# SYSTEM.net
KiCad netlist of a schematic drawn in Altium Designer
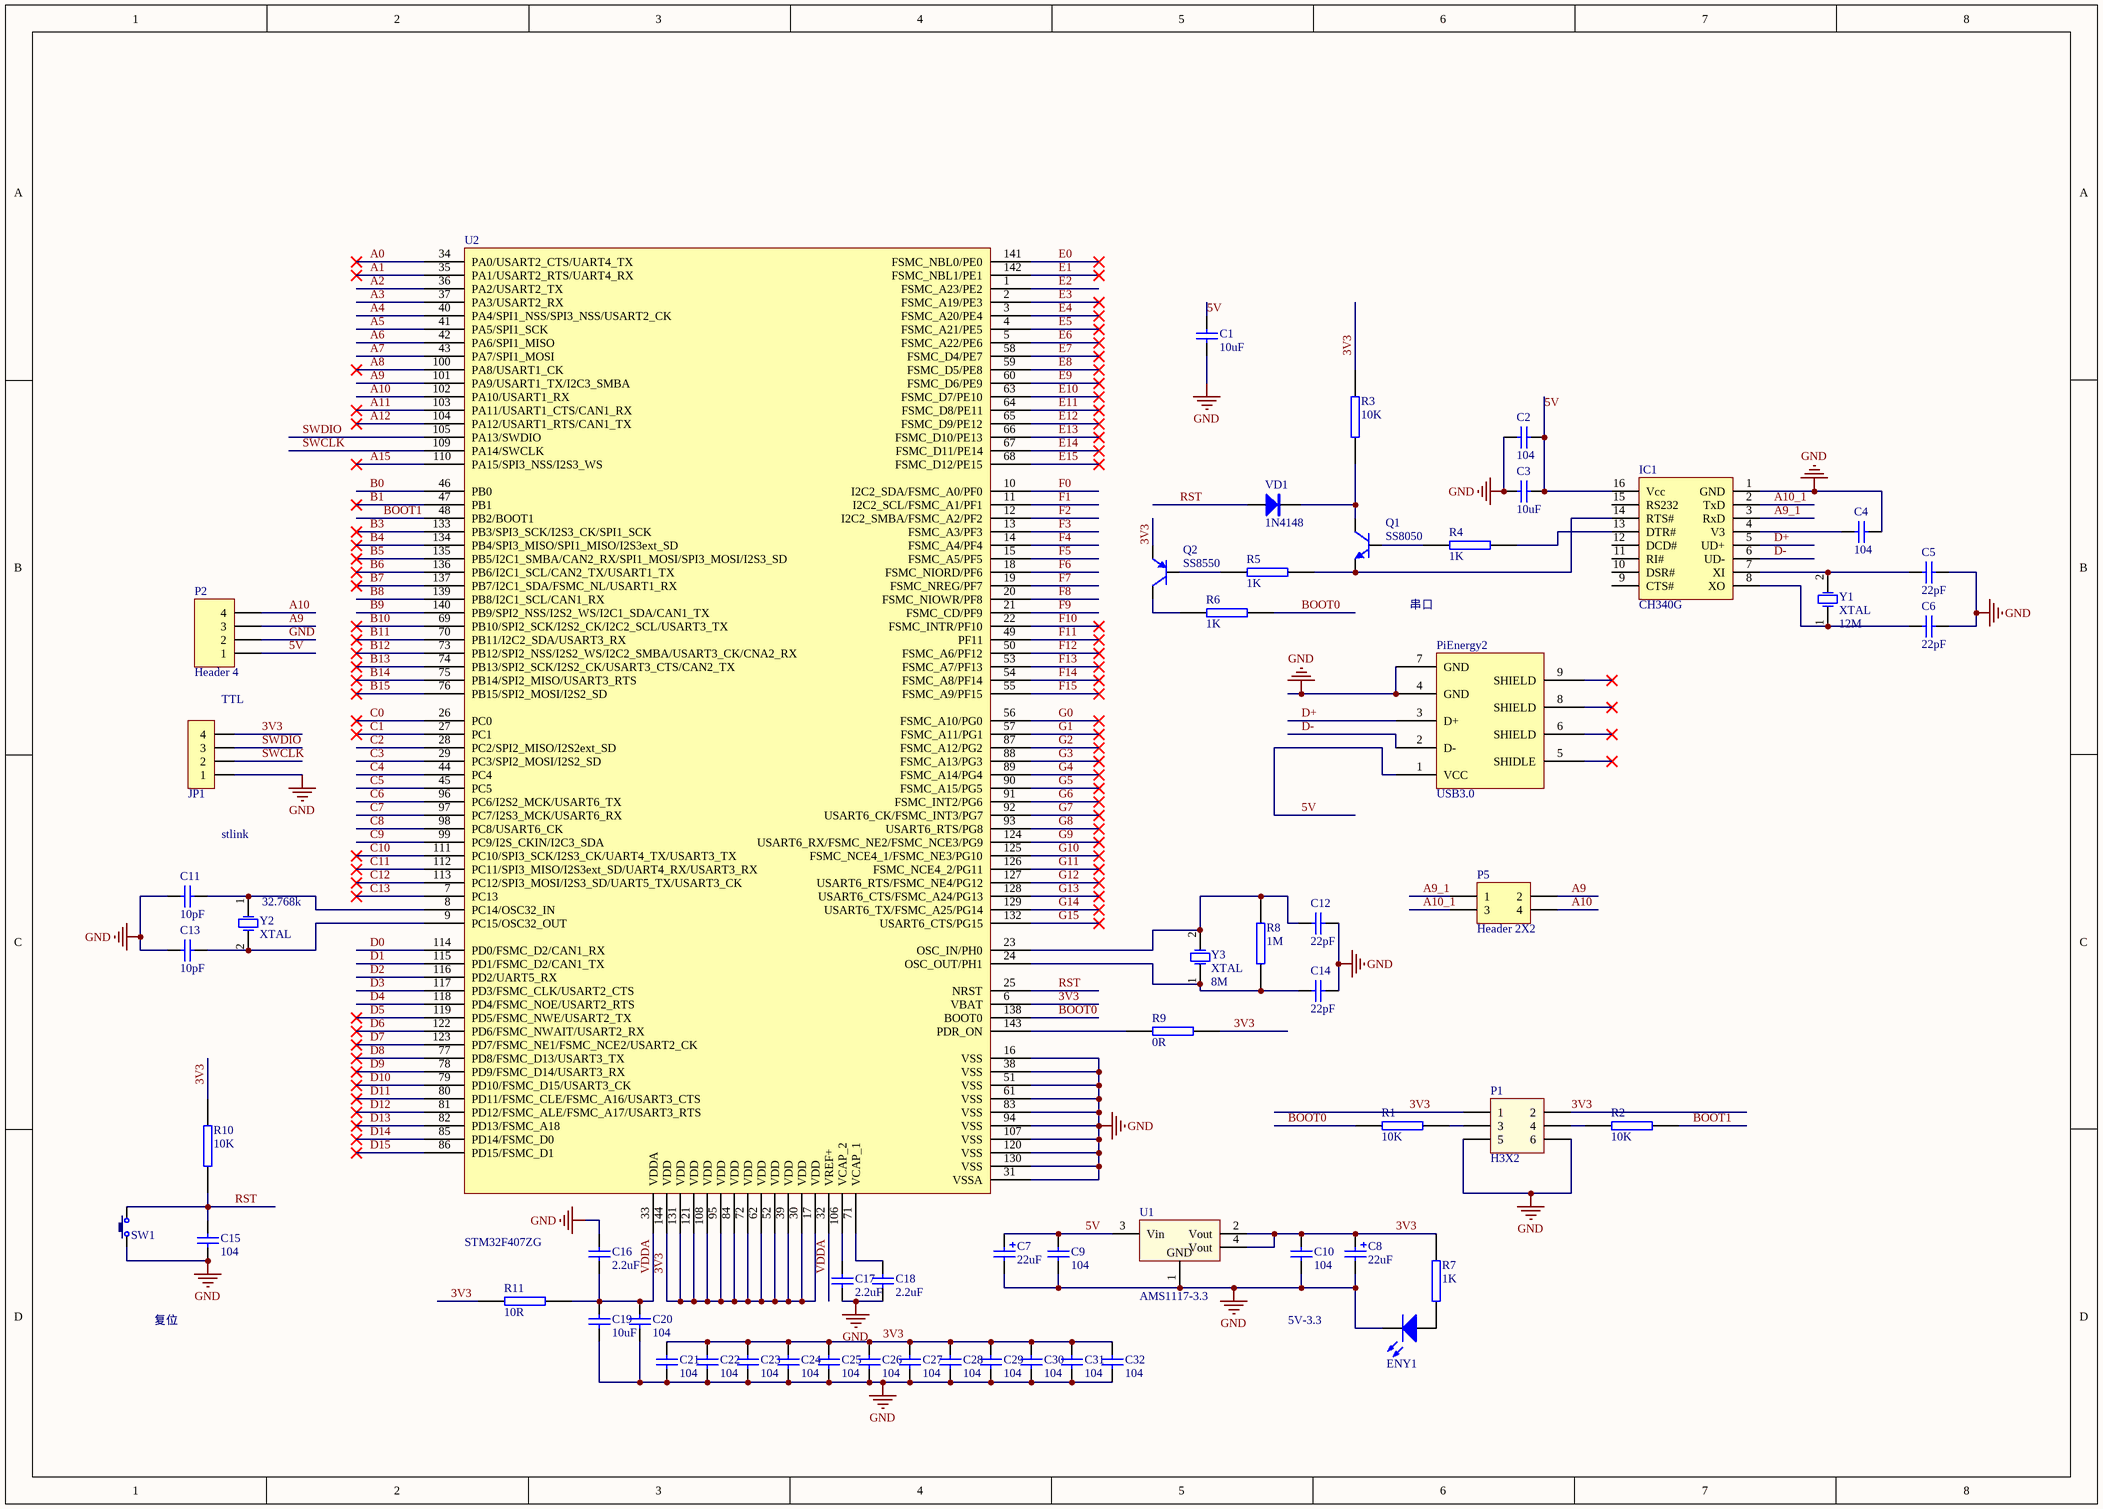
[diagram p0: SYSTEM.SchDoc]

(export (version "E")
  (design (tool "Eeschema 10.0.6"))
  (components
    (comp (ref "C1")
      (value "Cap")
      (footprint "CAP[0805]")
      (fields (field (name "ALTIUM_UNNAMED_1") "10uF"))
      (libsource (lib "STM32F103C8T6") (part "Cap"))
    )
    (comp (ref "C2")
      (value "Cap")
      (footprint "CAP[0805]")
      (fields (field (name "ALTIUM_UNNAMED_1") "104"))
      (libsource (lib "STM32F103C8T6") (part "Cap"))
    )
    (comp (ref "C3")
      (value "Cap")
      (footprint "CAP[0805]")
      (fields (field (name "ALTIUM_UNNAMED_1") "10uF"))
      (libsource (lib "STM32F103C8T6") (part "Cap"))
    )
    (comp (ref "C4")
      (value "Cap")
      (footprint "CAP[0805]")
      (fields (field (name "ALTIUM_UNNAMED_1") "104"))
      (libsource (lib "STM32F103C8T6") (part "Cap"))
    )
    (comp (ref "C5")
      (value "Cap")
      (footprint "CAP[0805]")
      (fields (field (name "ALTIUM_UNNAMED_1") "22pF"))
      (libsource (lib "STM32F103C8T6") (part "Cap"))
    )
    (comp (ref "C6")
      (value "Cap")
      (footprint "CAP[0805]")
      (fields (field (name "ALTIUM_UNNAMED_1") "22pF"))
      (libsource (lib "STM32F103C8T6") (part "Cap"))
    )
    (comp (ref "C7")
      (value "Cap Pol(22uF)")
      (footprint "CAP[1210]")
      (fields (field (name "ALTIUM_UNNAMED_1") "22uF"))
      (libsource (lib "STM32F103C8T6") (part "Cap Pol(22uF)"))
    )
    (comp (ref "C8")
      (value "Cap Pol(22uF)")
      (footprint "CAP[1210]")
      (fields (field (name "ALTIUM_UNNAMED_1") "22uF"))
      (libsource (lib "STM32F103C8T6") (part "Cap Pol(22uF)"))
    )
    (comp (ref "C9")
      (value "Cap")
      (footprint "CAP[0805]")
      (fields (field (name "ALTIUM_UNNAMED_1") "104"))
      (libsource (lib "STM32F103C8T6") (part "Cap"))
    )
    (comp (ref "C10")
      (value "Cap")
      (footprint "CAP[0805]")
      (fields (field (name "ALTIUM_UNNAMED_1") "104"))
      (libsource (lib "STM32F103C8T6") (part "Cap"))
    )
    (comp (ref "C11")
      (value "Cap")
      (footprint "CAP[0805]")
      (fields (field (name "ALTIUM_UNNAMED_1") "10pF"))
      (libsource (lib "STM32F103C8T6") (part "Cap"))
    )
    (comp (ref "C12")
      (value "Cap")
      (footprint "CAP[0805]")
      (fields (field (name "ALTIUM_UNNAMED_1") "22pF"))
      (libsource (lib "STM32F103C8T6") (part "Cap"))
    )
    (comp (ref "C13")
      (value "Cap")
      (footprint "CAP[0805]")
      (fields (field (name "ALTIUM_UNNAMED_1") "10pF"))
      (libsource (lib "STM32F103C8T6") (part "Cap"))
    )
    (comp (ref "C14")
      (value "Cap")
      (footprint "CAP[0805]")
      (fields (field (name "ALTIUM_UNNAMED_1") "22pF"))
      (libsource (lib "STM32F103C8T6") (part "Cap"))
    )
    (comp (ref "C15")
      (value "Cap")
      (footprint "CAP[0805]")
      (fields (field (name "ALTIUM_UNNAMED_1") "104"))
      (libsource (lib "STM32F103C8T6") (part "Cap"))
    )
    (comp (ref "C16")
      (value "Cap")
      (footprint "CAP[0805]")
      (fields (field (name "ALTIUM_UNNAMED_1") "2.2uF"))
      (libsource (lib "STM32F103C8T6") (part "Cap"))
    )
    (comp (ref "C17")
      (value "Cap")
      (footprint "CAP[0805]")
      (fields (field (name "ALTIUM_UNNAMED_1") "2.2uF"))
      (libsource (lib "STM32F103C8T6") (part "Cap"))
    )
    (comp (ref "C18")
      (value "Cap")
      (footprint "CAP[0805]")
      (fields (field (name "ALTIUM_UNNAMED_1") "2.2uF"))
      (libsource (lib "STM32F103C8T6") (part "Cap"))
    )
    (comp (ref "C19")
      (value "Cap")
      (footprint "CAP[0805]")
      (fields (field (name "ALTIUM_UNNAMED_1") "10uF"))
      (libsource (lib "STM32F103C8T6") (part "Cap"))
    )
    (comp (ref "C20")
      (value "Cap")
      (footprint "CAP[0805]")
      (fields (field (name "ALTIUM_UNNAMED_1") "104"))
      (libsource (lib "STM32F103C8T6") (part "Cap"))
    )
    (comp (ref "C21")
      (value "Cap")
      (footprint "CAP[0805]")
      (fields (field (name "ALTIUM_UNNAMED_1") "104"))
      (libsource (lib "STM32F103C8T6") (part "Cap"))
    )
    (comp (ref "C22")
      (value "Cap")
      (footprint "CAP[0805]")
      (fields (field (name "ALTIUM_UNNAMED_1") "104"))
      (libsource (lib "STM32F103C8T6") (part "Cap"))
    )
    (comp (ref "C23")
      (value "Cap")
      (footprint "CAP[0805]")
      (fields (field (name "ALTIUM_UNNAMED_1") "104"))
      (libsource (lib "STM32F103C8T6") (part "Cap"))
    )
    (comp (ref "C24")
      (value "Cap")
      (footprint "CAP[0805]")
      (fields (field (name "ALTIUM_UNNAMED_1") "104"))
      (libsource (lib "STM32F103C8T6") (part "Cap"))
    )
    (comp (ref "C25")
      (value "Cap")
      (footprint "CAP[0805]")
      (fields (field (name "ALTIUM_UNNAMED_1") "104"))
      (libsource (lib "STM32F103C8T6") (part "Cap"))
    )
    (comp (ref "C26")
      (value "Cap")
      (footprint "CAP[0805]")
      (fields (field (name "ALTIUM_UNNAMED_1") "104"))
      (libsource (lib "STM32F103C8T6") (part "Cap"))
    )
    (comp (ref "C27")
      (value "Cap")
      (footprint "CAP[0805]")
      (fields (field (name "ALTIUM_UNNAMED_1") "104"))
      (libsource (lib "STM32F103C8T6") (part "Cap"))
    )
    (comp (ref "C28")
      (value "Cap")
      (footprint "CAP[0805]")
      (fields (field (name "ALTIUM_UNNAMED_1") "104"))
      (libsource (lib "STM32F103C8T6") (part "Cap"))
    )
    (comp (ref "C29")
      (value "Cap")
      (footprint "CAP[0805]")
      (fields (field (name "ALTIUM_UNNAMED_1") "104"))
      (libsource (lib "STM32F103C8T6") (part "Cap"))
    )
    (comp (ref "C30")
      (value "Cap")
      (footprint "CAP[0805]")
      (fields (field (name "ALTIUM_UNNAMED_1") "104"))
      (libsource (lib "STM32F103C8T6") (part "Cap"))
    )
    (comp (ref "C31")
      (value "Cap")
      (footprint "CAP[0805]")
      (fields (field (name "ALTIUM_UNNAMED_1") "104"))
      (libsource (lib "STM32F103C8T6") (part "Cap"))
    )
    (comp (ref "C32")
      (value "Cap")
      (footprint "CAP[0805]")
      (fields (field (name "ALTIUM_UNNAMED_1") "104"))
      (libsource (lib "STM32F103C8T6") (part "Cap"))
    )
    (comp (ref "ENY1") (value "LED0") (footprint "LED[0805]") (libsource (lib "bob") (part "LED0")))
    (comp (ref "IC1")
      (value "CH340G")
      (footprint "SOP16_M")
      (description "串口转USB")
      (fields (field (name "版权归属") "源创客"))
      (libsource (lib "PCB_Project2") (part "CH340G"))
    )
    (comp (ref "JP1")
      (value "HDR-1X4")
      (footprint "HDR-1X4_M")
      (description "4P接插件")
      (fields (field (name "版权归属") "源创客"))
      (libsource (lib "PCB_Project2") (part "Header 4"))
    )
    (comp (ref "P1") (value "H3X2") (footprint "H2.54-2X3") (libsource (lib "STM32F103C8T6") (part "H3X2")))
    (comp (ref "P2")
      (value "Header 4")
      (footprint "HDR1X4")
      (description "Header, 4-Pin")
      (fields (field (name "PUBLISHER") "Altium Limited"))
      (libsource (lib "Miscellaneous Connectors") (part "Header 4"))
    )
    (comp (ref "P5")
      (value "Header 2X2")
      (footprint "HDR2X2")
      (description "Header, 2-Pin, Dual row")
      (fields (field (name "PUBLISHER") "Altium Limited"))
      (libsource (lib "Miscellaneous Connectors") (part "Header 2X2"))
    )
    (comp (ref "PiEnergy2") (value "USB3.0") (footprint "USB3.0") (libsource (lib "Robot") (part "USB3.0")))
    (comp (ref "Q1")
      (value "SS8050")
      (footprint "SOT23-3M")
      (description "高频放大-NPN型")
      (fields (field (name "版权归属") "源创客"))
      (libsource (lib "PCB_Project2") (part "8050-SMD"))
    )
    (comp (ref "Q2")
      (value "SS8550")
      (footprint "SOT23-3M")
      (description "高频放大-PNP型")
      (fields (field (name "版权归属") "源创客"))
      (libsource (lib "PCB_Project2") (part "8550-SMD"))
    )
    (comp (ref "R1") (value "10K") (footprint "R0805") (libsource (lib "STM32F103C8T6") (part "RES")))
    (comp (ref "R2") (value "10K") (footprint "R0805") (libsource (lib "STM32F103C8T6") (part "RES")))
    (comp (ref "R3") (value "10K") (footprint "R0805") (libsource (lib "STM32F103C8T6") (part "RES")))
    (comp (ref "R4") (value "1K") (footprint "R0805") (libsource (lib "STM32F103C8T6") (part "RES")))
    (comp (ref "R5") (value "1K") (footprint "R0805") (libsource (lib "STM32F103C8T6") (part "RES")))
    (comp (ref "R6") (value "1K") (footprint "R0805") (libsource (lib "STM32F103C8T6") (part "RES")))
    (comp (ref "R7") (value "1K") (footprint "R0805") (libsource (lib "bob") (part "RES")))
    (comp (ref "R8") (value "1M") (footprint "R0805") (libsource (lib "STM32F103C8T6") (part "RES")))
    (comp (ref "R9") (value "0R") (footprint "R0805") (libsource (lib "STM32F103C8T6") (part "RES")))
    (comp (ref "R10") (value "10K") (footprint "R0805") (libsource (lib "STM32F103C8T6") (part "RES")))
    (comp (ref "R11") (value "10R") (footprint "R0805") (libsource (lib "STM32F103C8T6") (part "RES")))
    (comp (ref "SW1")
      (value "3x6x5")
      (footprint "TSW SMD-3*6*2.5")
      (description "3x6轻触开关")
      (fields (field (name "版权归属") "源创客"))
      (libsource (lib "bob") (part "TSW 3x6"))
    )
    (comp (ref "U1")
      (value "AMS1117-3.3")
      (footprint "SOT-223(AMS1117-3.3)")
      (libsource (lib "STM32F103C8T6") (part "AMS1117-3.3"))
    )
    (comp (ref "U2")
      (value "STM32F407ZG")
      (footprint "LQFP144 20X20_M")
      (description "Flaah:1024/RAM:192/IO:114")
      (fields (field (name "版权归属") "源创客"))
      (libsource (lib "PCB_Project2") (part "STM32F407ZG"))
    )
    (comp (ref "VD1")
      (value "1N4148")
      (footprint "MINI_MELF (LL34)")
      (description "高速开关二极管")
      (fields (field (name "版权归属") "源创客"))
      (libsource (lib "PCB_Project2") (part "1N4148"))
    )
    (comp (ref "Y1")
      (value "XTAL")
      (footprint "XTAL")
      (fields (field (name "ALTIUM_UNNAMED_1") "12M"))
      (libsource (lib "STM32F103C8T6") (part "XTAL_1"))
    )
    (comp (ref "Y2")
      (value "XTAL")
      (footprint "XTAL-DT38-SMD")
      (fields (field (name "ALTIUM_UNNAMED_1") "32.768k"))
      (libsource (lib "STM32F103C8T6") (part "XTAL"))
    )
    (comp (ref "Y3")
      (value "XTAL")
      (footprint "XTAL")
      (fields (field (name "ALTIUM_UNNAMED_1") "8M"))
      (libsource (lib "STM32F103C8T6") (part "XTAL_1"))
    )
  )
  (nets
    (net (code "1") (name "/3V3") (class "Default")
      (node (ref "C10") (pin "2") (pinfunction "2_2") (pintype "passive"))
      (node (ref "C21") (pin "2") (pinfunction "2_2") (pintype "passive"))
      (node (ref "C22") (pin "2") (pinfunction "2_2") (pintype "passive"))
      (node (ref "C23") (pin "2") (pinfunction "2_2") (pintype "passive"))
      (node (ref "C24") (pin "2") (pinfunction "2_2") (pintype "passive"))
      (node (ref "C25") (pin "2") (pinfunction "2_2") (pintype "passive"))
      (node (ref "C26") (pin "2") (pinfunction "2_2") (pintype "passive"))
      (node (ref "C27") (pin "2") (pinfunction "2_2") (pintype "passive"))
      (node (ref "C28") (pin "2") (pinfunction "2_2") (pintype "passive"))
      (node (ref "C29") (pin "2") (pinfunction "2_2") (pintype "passive"))
      (node (ref "C30") (pin "2") (pinfunction "2_2") (pintype "passive"))
      (node (ref "C31") (pin "2") (pinfunction "2_2") (pintype "passive"))
      (node (ref "C32") (pin "2") (pinfunction "2_2") (pintype "passive"))
      (node (ref "C8") (pin "1") (pinfunction "1_1") (pintype "passive"))
      (node (ref "JP1") (pin "4") (pinfunction "4_4") (pintype "passive"))
      (node (ref "P1") (pin "1") (pinfunction "1_1") (pintype "passive"))
      (node (ref "P1") (pin "2") (pinfunction "2_2") (pintype "passive"))
      (node (ref "Q2") (pin "2") (pinfunction "E_2") (pintype "passive"))
      (node (ref "R10") (pin "2") (pinfunction "2_2") (pintype "passive"))
      (node (ref "R11") (pin "1") (pinfunction "1_1") (pintype "passive"))
      (node (ref "R3") (pin "2") (pinfunction "2_2") (pintype "passive"))
      (node (ref "R7") (pin "2") (pinfunction "2_2") (pintype "passive"))
      (node (ref "R9") (pin "2") (pinfunction "2_2") (pintype "passive"))
      (node (ref "U1") (pin "2") (pinfunction "Vout_2") (pintype "passive"))
      (node (ref "U1") (pin "4") (pinfunction "Vout_4") (pintype "passive"))
      (node (ref "U2") (pin "108") (pinfunction "VDD_108") (pintype "passive"))
      (node (ref "U2") (pin "121") (pinfunction "VDD_121") (pintype "passive"))
      (node (ref "U2") (pin "131") (pinfunction "VDD_131") (pintype "passive"))
      (node (ref "U2") (pin "144") (pinfunction "VDD_144") (pintype "passive"))
      (node (ref "U2") (pin "17") (pinfunction "VDD_17") (pintype "passive"))
      (node (ref "U2") (pin "30") (pinfunction "VDD_30") (pintype "passive"))
      (node (ref "U2") (pin "39") (pinfunction "VDD_39") (pintype "passive"))
      (node (ref "U2") (pin "52") (pinfunction "VDD_52") (pintype "passive"))
      (node (ref "U2") (pin "6") (pinfunction "VBAT_6") (pintype "passive"))
      (node (ref "U2") (pin "62") (pinfunction "VDD_62") (pintype "passive"))
      (node (ref "U2") (pin "72") (pinfunction "VDD_72") (pintype "passive"))
      (node (ref "U2") (pin "84") (pinfunction "VDD_84") (pintype "passive"))
      (node (ref "U2") (pin "95") (pinfunction "VDD_95") (pintype "passive"))
    )
    (net (code "2") (name "/5V") (class "Default")
      (node (ref "C1") (pin "2") (pinfunction "2_2") (pintype "passive"))
      (node (ref "C2") (pin "2") (pinfunction "2_2") (pintype "passive"))
      (node (ref "C3") (pin "2") (pinfunction "2_2") (pintype "passive"))
      (node (ref "C7") (pin "1") (pinfunction "1_1") (pintype "passive"))
      (node (ref "C9") (pin "2") (pinfunction "2_2") (pintype "passive"))
      (node (ref "IC1") (pin "16") (pinfunction "Vcc_16") (pintype "passive"))
      (node (ref "P2") (pin "1") (pinfunction "1_1") (pintype "passive"))
      (node (ref "PiEnergy2") (pin "1") (pinfunction "VCC_1") (pintype "passive"))
      (node (ref "U1") (pin "3") (pinfunction "Vin_3") (pintype "passive"))
    )
    (net (code "3") (name "/A0") (class "Default")
      (node (ref "U2") (pin "34") (pinfunction "PA0/USART2_CTS/UART4_TX_34") (pintype "passive+no_connect"))
    )
    (net (code "4") (name "/A1") (class "Default")
      (node (ref "U2") (pin "35") (pinfunction "PA1/USART2_RTS/UART4_RX_35") (pintype "passive+no_connect"))
    )
    (net (code "5") (name "/A2") (class "Default")
      (node (ref "U2") (pin "36") (pinfunction "PA2/USART2_TX_36") (pintype "passive"))
    )
    (net (code "6") (name "/A3") (class "Default")
      (node (ref "U2") (pin "37") (pinfunction "PA3/USART2_RX_37") (pintype "passive"))
    )
    (net (code "7") (name "/A4") (class "Default")
      (node (ref "U2") (pin "40") (pinfunction "PA4/SPI1_NSS/SPI3_NSS/USART2_CK_40") (pintype "passive"))
    )
    (net (code "8") (name "/A5") (class "Default")
      (node (ref "U2") (pin "41") (pinfunction "PA5/SPI1_SCK_41") (pintype "passive"))
    )
    (net (code "9") (name "/A6") (class "Default")
      (node (ref "U2") (pin "42") (pinfunction "PA6/SPI1_MISO_42") (pintype "passive"))
    )
    (net (code "10") (name "/A7") (class "Default")
      (node (ref "U2") (pin "43") (pinfunction "PA7/SPI1_MOSI_43") (pintype "passive"))
    )
    (net (code "11") (name "/A8") (class "Default")
      (node (ref "U2") (pin "100") (pinfunction "PA8/USART1_CK_100") (pintype "passive+no_connect"))
    )
    (net (code "12") (name "/A9") (class "Default")
      (node (ref "P2") (pin "3") (pinfunction "3_3") (pintype "passive"))
      (node (ref "P5") (pin "2") (pinfunction "2_2") (pintype "passive"))
      (node (ref "U2") (pin "101") (pinfunction "PA9/USART1_TX/I2C3_SMBA_101") (pintype "passive"))
    )
    (net (code "13") (name "/A9_1") (class "Default")
      (node (ref "IC1") (pin "3") (pinfunction "RxD_3") (pintype "passive"))
      (node (ref "P5") (pin "1") (pinfunction "1_1") (pintype "passive"))
    )
    (net (code "14") (name "/A10") (class "Default")
      (node (ref "P2") (pin "4") (pinfunction "4_4") (pintype "passive"))
      (node (ref "P5") (pin "4") (pinfunction "4_4") (pintype "passive"))
      (node (ref "U2") (pin "102") (pinfunction "PA10/USART1_RX_102") (pintype "passive"))
    )
    (net (code "15") (name "/A10_1") (class "Default")
      (node (ref "IC1") (pin "2") (pinfunction "TxD_2") (pintype "passive"))
      (node (ref "P5") (pin "3") (pinfunction "3_3") (pintype "passive"))
    )
    (net (code "16") (name "/A11") (class "Default")
      (node (ref "U2") (pin "103") (pinfunction "PA11/USART1_CTS/CAN1_RX_103") (pintype "passive+no_connect"))
    )
    (net (code "17") (name "/A12") (class "Default")
      (node (ref "U2") (pin "104") (pinfunction "PA12/USART1_RTS/CAN1_TX_104") (pintype "passive+no_connect"))
    )
    (net (code "18") (name "/A15") (class "Default")
      (node (ref "U2") (pin "110") (pinfunction "PA15/SPI3_NSS/I2S3_WS_110") (pintype "passive+no_connect"))
    )
    (net (code "19") (name "/B0") (class "Default")
      (node (ref "U2") (pin "46") (pinfunction "PB0_46") (pintype "passive"))
    )
    (net (code "20") (name "/B1") (class "Default")
      (node (ref "U2") (pin "47") (pinfunction "PB1_47") (pintype "passive+no_connect"))
    )
    (net (code "21") (name "/B3") (class "Default")
      (node (ref "U2") (pin "133") (pinfunction "PB3/SPI3_SCK/I2S3_CK/SPI1_SCK_133") (pintype "passive+no_connect"))
    )
    (net (code "22") (name "/B4") (class "Default")
      (node (ref "U2") (pin "134") (pinfunction "PB4/SPI3_MISO/SPI1_MISO/I2S3ext_SD_134") (pintype "passive+no_connect"))
    )
    (net (code "23") (name "/B5") (class "Default")
      (node (ref "U2") (pin "135") (pinfunction "PB5/I2C1_SMBA/CAN2_RX/SPI1_MOSI/SPI3_MOSI/I2S3_SD_135") (pintype "passive+no_connect"))
    )
    (net (code "24") (name "/B6") (class "Default")
      (node (ref "U2") (pin "136") (pinfunction "PB6/I2C1_SCL/CAN2_TX/USART1_TX_136") (pintype "passive+no_connect"))
    )
    (net (code "25") (name "/B7") (class "Default")
      (node (ref "U2") (pin "137") (pinfunction "PB7/I2C1_SDA/FSMC_NL/USART1_RX_137") (pintype "passive+no_connect"))
    )
    (net (code "26") (name "/B8") (class "Default")
      (node (ref "U2") (pin "139") (pinfunction "PB8/I2C1_SCL/CAN1_RX_139") (pintype "passive"))
    )
    (net (code "27") (name "/B9") (class "Default")
      (node (ref "U2") (pin "140") (pinfunction "PB9/SPI2_NSS/I2S2_WS/I2C1_SDA/CAN1_TX_140") (pintype "passive"))
    )
    (net (code "28") (name "/B10") (class "Default")
      (node (ref "U2") (pin "69") (pinfunction "PB10/SPI2_SCK/I2S2_CK/I2C2_SCL/USART3_TX_69") (pintype "passive+no_connect"))
    )
    (net (code "29") (name "/B11") (class "Default")
      (node (ref "U2") (pin "70") (pinfunction "PB11/I2C2_SDA/USART3_RX_70") (pintype "passive+no_connect"))
    )
    (net (code "30") (name "/B12") (class "Default")
      (node (ref "U2") (pin "73") (pinfunction "PB12/SPI2_NSS/I2S2_WS/I2C2_SMBA/USART3_CK/CNA2_RX_73") (pintype "passive+no_connect"))
    )
    (net (code "31") (name "/B13") (class "Default")
      (node (ref "U2") (pin "74") (pinfunction "PB13/SPI2_SCK/I2S2_CK/USART3_CTS/CAN2_TX_74") (pintype "passive+no_connect"))
    )
    (net (code "32") (name "/B14") (class "Default")
      (node (ref "U2") (pin "75") (pinfunction "PB14/SPI2_MISO/USART3_RTS_75") (pintype "passive+no_connect"))
    )
    (net (code "33") (name "/B15") (class "Default")
      (node (ref "U2") (pin "76") (pinfunction "PB15/SPI2_MOSI/I2S2_SD_76") (pintype "passive+no_connect"))
    )
    (net (code "34") (name "/BOOT0") (class "Default")
      (node (ref "R1") (pin "1") (pinfunction "1_1") (pintype "passive"))
      (node (ref "R6") (pin "1") (pinfunction "1_1") (pintype "passive"))
      (node (ref "U2") (pin "138") (pinfunction "BOOT0_138") (pintype "passive"))
    )
    (net (code "35") (name "/BOOT1") (class "Default")
      (node (ref "R2") (pin "2") (pinfunction "2_2") (pintype "passive"))
      (node (ref "U2") (pin "48") (pinfunction "PB2/BOOT1_48") (pintype "passive"))
    )
    (net (code "36") (name "/C0") (class "Default")
      (node (ref "U2") (pin "26") (pinfunction "PC0_26") (pintype "passive+no_connect"))
    )
    (net (code "37") (name "/C1") (class "Default")
      (node (ref "U2") (pin "27") (pinfunction "PC1_27") (pintype "passive+no_connect"))
    )
    (net (code "38") (name "/C2") (class "Default")
      (node (ref "U2") (pin "28") (pinfunction "PC2/SPI2_MISO/I2S2ext_SD_28") (pintype "passive"))
    )
    (net (code "39") (name "/C3") (class "Default")
      (node (ref "U2") (pin "29") (pinfunction "PC3/SPI2_MOSI/I2S2_SD_29") (pintype "passive"))
    )
    (net (code "40") (name "/C4") (class "Default")
      (node (ref "U2") (pin "44") (pinfunction "PC4_44") (pintype "passive"))
    )
    (net (code "41") (name "/C5") (class "Default")
      (node (ref "U2") (pin "45") (pinfunction "PC5_45") (pintype "passive"))
    )
    (net (code "42") (name "/C6") (class "Default")
      (node (ref "U2") (pin "96") (pinfunction "PC6/I2S2_MCK/USART6_TX_96") (pintype "passive"))
    )
    (net (code "43") (name "/C7") (class "Default")
      (node (ref "U2") (pin "97") (pinfunction "PC7/I2S3_MCK/USART6_RX_97") (pintype "passive"))
    )
    (net (code "44") (name "/C8") (class "Default")
      (node (ref "U2") (pin "98") (pinfunction "PC8/USART6_CK_98") (pintype "passive"))
    )
    (net (code "45") (name "/C9") (class "Default")
      (node (ref "U2") (pin "99") (pinfunction "PC9/I2S_CKIN/I2C3_SDA_99") (pintype "passive"))
    )
    (net (code "46") (name "/C10") (class "Default")
      (node (ref "U2") (pin "111") (pinfunction "PC10/SPI3_SCK/I2S3_CK/UART4_TX/USART3_TX_111") (pintype "passive+no_connect"))
    )
    (net (code "47") (name "/C11") (class "Default")
      (node (ref "U2") (pin "112") (pinfunction "PC11/SPI3_MISO/I2S3ext_SD/UART4_RX/USART3_RX_112") (pintype "passive+no_connect"))
    )
    (net (code "48") (name "/C12") (class "Default")
      (node (ref "U2") (pin "113") (pinfunction "PC12/SPI3_MOSI/I2S3_SD/UART5_TX/USART3_CK_113") (pintype "passive+no_connect"))
    )
    (net (code "49") (name "/C13") (class "Default")
      (node (ref "U2") (pin "7") (pinfunction "PC13_7") (pintype "passive+no_connect"))
    )
    (net (code "50") (name "/D+") (class "Default")
      (node (ref "IC1") (pin "5") (pinfunction "UD+_5") (pintype "passive"))
      (node (ref "PiEnergy2") (pin "3") (pinfunction "D+_3") (pintype "passive"))
    )
    (net (code "51") (name "/D-") (class "Default")
      (node (ref "IC1") (pin "6") (pinfunction "UD-_6") (pintype "passive"))
      (node (ref "PiEnergy2") (pin "2") (pinfunction "D-_2") (pintype "passive"))
    )
    (net (code "52") (name "/D0") (class "Default")
      (node (ref "U2") (pin "114") (pinfunction "PD0/FSMC_D2/CAN1_RX_114") (pintype "passive"))
    )
    (net (code "53") (name "/D1") (class "Default")
      (node (ref "U2") (pin "115") (pinfunction "PD1/FSMC_D2/CAN1_TX_115") (pintype "passive"))
    )
    (net (code "54") (name "/D2") (class "Default")
      (node (ref "U2") (pin "116") (pinfunction "PD2/UART5_RX_116") (pintype "passive"))
    )
    (net (code "55") (name "/D3") (class "Default")
      (node (ref "U2") (pin "117") (pinfunction "PD3/FSMC_CLK/USART2_CTS_117") (pintype "passive"))
    )
    (net (code "56") (name "/D4") (class "Default")
      (node (ref "U2") (pin "118") (pinfunction "PD4/FSMC_NOE/USART2_RTS_118") (pintype "passive"))
    )
    (net (code "57") (name "/D5") (class "Default")
      (node (ref "U2") (pin "119") (pinfunction "PD5/FSMC_NWE/USART2_TX_119") (pintype "passive+no_connect"))
    )
    (net (code "58") (name "/D6") (class "Default")
      (node (ref "U2") (pin "122") (pinfunction "PD6/FSMC_NWAIT/USART2_RX_122") (pintype "passive+no_connect"))
    )
    (net (code "59") (name "/D7") (class "Default")
      (node (ref "U2") (pin "123") (pinfunction "PD7/FSMC_NE1/FSMC_NCE2/USART2_CK_123") (pintype "passive+no_connect"))
    )
    (net (code "60") (name "/D8") (class "Default")
      (node (ref "U2") (pin "77") (pinfunction "PD8/FSMC_D13/USART3_TX_77") (pintype "passive+no_connect"))
    )
    (net (code "61") (name "/D9") (class "Default")
      (node (ref "U2") (pin "78") (pinfunction "PD9/FSMC_D14/USART3_RX_78") (pintype "passive+no_connect"))
    )
    (net (code "62") (name "/D10") (class "Default")
      (node (ref "U2") (pin "79") (pinfunction "PD10/FSMC_D15/USART3_CK_79") (pintype "passive+no_connect"))
    )
    (net (code "63") (name "/D11") (class "Default")
      (node (ref "U2") (pin "80") (pinfunction "PD11/FSMC_CLE/FSMC_A16/USART3_CTS_80") (pintype "passive+no_connect"))
    )
    (net (code "64") (name "/D12") (class "Default")
      (node (ref "U2") (pin "81") (pinfunction "PD12/FSMC_ALE/FSMC_A17/USART3_RTS_81") (pintype "passive+no_connect"))
    )
    (net (code "65") (name "/D13") (class "Default")
      (node (ref "U2") (pin "82") (pinfunction "PD13/FSMC_A18_82") (pintype "passive+no_connect"))
    )
    (net (code "66") (name "/D14") (class "Default")
      (node (ref "U2") (pin "85") (pinfunction "PD14/FSMC_D0_85") (pintype "passive+no_connect"))
    )
    (net (code "67") (name "/D15") (class "Default")
      (node (ref "U2") (pin "86") (pinfunction "PD15/FSMC_D1_86") (pintype "passive+no_connect"))
    )
    (net (code "68") (name "/E0") (class "Default")
      (node (ref "U2") (pin "141") (pinfunction "FSMC_NBL0/PE0_141") (pintype "passive+no_connect"))
    )
    (net (code "69") (name "/E1") (class "Default")
      (node (ref "U2") (pin "142") (pinfunction "FSMC_NBL1/PE1_142") (pintype "passive+no_connect"))
    )
    (net (code "70") (name "/E2") (class "Default")
      (node (ref "U2") (pin "1") (pinfunction "FSMC_A23/PE2_1") (pintype "passive"))
    )
    (net (code "71") (name "/E3") (class "Default")
      (node (ref "U2") (pin "2") (pinfunction "FSMC_A19/PE3_2") (pintype "passive+no_connect"))
    )
    (net (code "72") (name "/E4") (class "Default")
      (node (ref "U2") (pin "3") (pinfunction "FSMC_A20/PE4_3") (pintype "passive+no_connect"))
    )
    (net (code "73") (name "/E5") (class "Default")
      (node (ref "U2") (pin "4") (pinfunction "FSMC_A21/PE5_4") (pintype "passive+no_connect"))
    )
    (net (code "74") (name "/E6") (class "Default")
      (node (ref "U2") (pin "5") (pinfunction "FSMC_A22/PE6_5") (pintype "passive+no_connect"))
    )
    (net (code "75") (name "/E7") (class "Default")
      (node (ref "U2") (pin "58") (pinfunction "FSMC_D4/PE7_58") (pintype "passive+no_connect"))
    )
    (net (code "76") (name "/E8") (class "Default")
      (node (ref "U2") (pin "59") (pinfunction "FSMC_D5/PE8_59") (pintype "passive+no_connect"))
    )
    (net (code "77") (name "/E9") (class "Default")
      (node (ref "U2") (pin "60") (pinfunction "FSMC_D6/PE9_60") (pintype "passive+no_connect"))
    )
    (net (code "78") (name "/E10") (class "Default")
      (node (ref "U2") (pin "63") (pinfunction "FSMC_D7/PE10_63") (pintype "passive+no_connect"))
    )
    (net (code "79") (name "/E11") (class "Default")
      (node (ref "U2") (pin "64") (pinfunction "FSMC_D8/PE11_64") (pintype "passive+no_connect"))
    )
    (net (code "80") (name "/E12") (class "Default")
      (node (ref "U2") (pin "65") (pinfunction "FSMC_D9/PE12_65") (pintype "passive+no_connect"))
    )
    (net (code "81") (name "/E13") (class "Default")
      (node (ref "U2") (pin "66") (pinfunction "FSMC_D10/PE13_66") (pintype "passive+no_connect"))
    )
    (net (code "82") (name "/E14") (class "Default")
      (node (ref "U2") (pin "67") (pinfunction "FSMC_D11/PE14_67") (pintype "passive+no_connect"))
    )
    (net (code "83") (name "/E15") (class "Default")
      (node (ref "U2") (pin "68") (pinfunction "FSMC_D12/PE15_68") (pintype "passive+no_connect"))
    )
    (net (code "84") (name "/F0") (class "Default")
      (node (ref "U2") (pin "10") (pinfunction "I2C2_SDA/FSMC_A0/PF0_10") (pintype "passive"))
    )
    (net (code "85") (name "/F1") (class "Default")
      (node (ref "U2") (pin "11") (pinfunction "I2C2_SCL/FSMC_A1/PF1_11") (pintype "passive"))
    )
    (net (code "86") (name "/F2") (class "Default")
      (node (ref "U2") (pin "12") (pinfunction "I2C2_SMBA/FSMC_A2/PF2_12") (pintype "passive"))
    )
    (net (code "87") (name "/F3") (class "Default")
      (node (ref "U2") (pin "13") (pinfunction "FSMC_A3/PF3_13") (pintype "passive"))
    )
    (net (code "88") (name "/F4") (class "Default")
      (node (ref "U2") (pin "14") (pinfunction "FSMC_A4/PF4_14") (pintype "passive"))
    )
    (net (code "89") (name "/F5") (class "Default")
      (node (ref "U2") (pin "15") (pinfunction "FSMC_A5/PF5_15") (pintype "passive"))
    )
    (net (code "90") (name "/F6") (class "Default")
      (node (ref "U2") (pin "18") (pinfunction "FSMC_NIORD/PF6_18") (pintype "passive"))
    )
    (net (code "91") (name "/F7") (class "Default")
      (node (ref "U2") (pin "19") (pinfunction "FSMC_NREG/PF7_19") (pintype "passive"))
    )
    (net (code "92") (name "/F8") (class "Default")
      (node (ref "U2") (pin "20") (pinfunction "FSMC_NIOWR/PF8_20") (pintype "passive"))
    )
    (net (code "93") (name "/F9") (class "Default")
      (node (ref "U2") (pin "21") (pinfunction "FSMC_CD/PF9_21") (pintype "passive"))
    )
    (net (code "94") (name "/F10") (class "Default")
      (node (ref "U2") (pin "22") (pinfunction "FSMC_INTR/PF10_22") (pintype "passive+no_connect"))
    )
    (net (code "95") (name "/F11") (class "Default")
      (node (ref "U2") (pin "49") (pinfunction "PF11_49") (pintype "passive+no_connect"))
    )
    (net (code "96") (name "/F12") (class "Default")
      (node (ref "U2") (pin "50") (pinfunction "FSMC_A6/PF12_50") (pintype "passive+no_connect"))
    )
    (net (code "97") (name "/F13") (class "Default")
      (node (ref "U2") (pin "53") (pinfunction "FSMC_A7/PF13_53") (pintype "passive+no_connect"))
    )
    (net (code "98") (name "/F14") (class "Default")
      (node (ref "U2") (pin "54") (pinfunction "FSMC_A8/PF14_54") (pintype "passive+no_connect"))
    )
    (net (code "99") (name "/F15") (class "Default")
      (node (ref "U2") (pin "55") (pinfunction "FSMC_A9/PF15_55") (pintype "passive+no_connect"))
    )
    (net (code "100") (name "/G0") (class "Default")
      (node (ref "U2") (pin "56") (pinfunction "FSMC_A10/PG0_56") (pintype "passive+no_connect"))
    )
    (net (code "101") (name "/G1") (class "Default")
      (node (ref "U2") (pin "57") (pinfunction "FSMC_A11/PG1_57") (pintype "passive+no_connect"))
    )
    (net (code "102") (name "/G2") (class "Default")
      (node (ref "U2") (pin "87") (pinfunction "FSMC_A12/PG2_87") (pintype "passive+no_connect"))
    )
    (net (code "103") (name "/G3") (class "Default")
      (node (ref "U2") (pin "88") (pinfunction "FSMC_A13/PG3_88") (pintype "passive+no_connect"))
    )
    (net (code "104") (name "/G4") (class "Default")
      (node (ref "U2") (pin "89") (pinfunction "FSMC_A14/PG4_89") (pintype "passive+no_connect"))
    )
    (net (code "105") (name "/G5") (class "Default")
      (node (ref "U2") (pin "90") (pinfunction "FSMC_A15/PG5_90") (pintype "passive+no_connect"))
    )
    (net (code "106") (name "/G6") (class "Default")
      (node (ref "U2") (pin "91") (pinfunction "FSMC_INT2/PG6_91") (pintype "passive+no_connect"))
    )
    (net (code "107") (name "/G7") (class "Default")
      (node (ref "U2") (pin "92") (pinfunction "USART6_CK/FSMC_INT3/PG7_92") (pintype "passive+no_connect"))
    )
    (net (code "108") (name "/G8") (class "Default")
      (node (ref "U2") (pin "93") (pinfunction "USART6_RTS/PG8_93") (pintype "passive+no_connect"))
    )
    (net (code "109") (name "/G9") (class "Default")
      (node (ref "U2") (pin "124") (pinfunction "USART6_RX/FSMC_NE2/FSMC_NCE3/PG9_124") (pintype "passive+no_connect"))
    )
    (net (code "110") (name "/G10") (class "Default")
      (node (ref "U2") (pin "125") (pinfunction "FSMC_NCE4_1/FSMC_NE3/PG10_125") (pintype "passive+no_connect"))
    )
    (net (code "111") (name "/G11") (class "Default")
      (node (ref "U2") (pin "126") (pinfunction "FSMC_NCE4_2/PG11_126") (pintype "passive+no_connect"))
    )
    (net (code "112") (name "/G12") (class "Default")
      (node (ref "U2") (pin "127") (pinfunction "USART6_RTS/FSMC_NE4/PG12_127") (pintype "passive+no_connect"))
    )
    (net (code "113") (name "/G13") (class "Default")
      (node (ref "U2") (pin "128") (pinfunction "USART6_CTS/FSMC_A24/PG13_128") (pintype "passive+no_connect"))
    )
    (net (code "114") (name "/G14") (class "Default")
      (node (ref "U2") (pin "129") (pinfunction "USART6_TX/FSMC_A25/PG14_129") (pintype "passive+no_connect"))
    )
    (net (code "115") (name "/G15") (class "Default")
      (node (ref "U2") (pin "132") (pinfunction "USART6_CTS/PG15_132") (pintype "passive+no_connect"))
    )
    (net (code "116") (name "/RST") (class "Default")
      (node (ref "C15") (pin "2") (pinfunction "2_2") (pintype "passive"))
      (node (ref "R10") (pin "1") (pinfunction "1_1") (pintype "passive"))
      (node (ref "SW1") (pin "2") (pinfunction "2_2") (pintype "passive"))
      (node (ref "U2") (pin "25") (pinfunction "NRST_25") (pintype "passive"))
      (node (ref "VD1") (pin "1") (pinfunction "A_1") (pintype "passive"))
    )
    (net (code "117") (name "/SWCLK") (class "Default")
      (node (ref "JP1") (pin "2") (pinfunction "2_2") (pintype "passive"))
      (node (ref "U2") (pin "109") (pinfunction "PA14/SWCLK_109") (pintype "passive"))
    )
    (net (code "118") (name "/SWDIO") (class "Default")
      (node (ref "JP1") (pin "3") (pinfunction "3_3") (pintype "passive"))
      (node (ref "U2") (pin "105") (pinfunction "PA13/SWDIO_105") (pintype "passive"))
    )
    (net (code "119") (name "/VDDA") (class "Default")
      (node (ref "C16") (pin "1") (pinfunction "1_1") (pintype "passive"))
      (node (ref "C19") (pin "2") (pinfunction "2_2") (pintype "passive"))
      (node (ref "C20") (pin "2") (pinfunction "2_2") (pintype "passive"))
      (node (ref "R11") (pin "2") (pinfunction "2_2") (pintype "passive"))
      (node (ref "U2") (pin "32") (pinfunction "VREF+_32") (pintype "passive"))
      (node (ref "U2") (pin "33") (pinfunction "VDDA_33") (pintype "passive"))
    )
    (net (code "120") (name "GND") (class "Default")
      (node (ref "C1") (pin "1") (pinfunction "1_1") (pintype "passive"))
      (node (ref "C10") (pin "1") (pinfunction "1_1") (pintype "passive"))
      (node (ref "C11") (pin "1") (pinfunction "1_1") (pintype "passive"))
      (node (ref "C12") (pin "2") (pinfunction "2_2") (pintype "passive"))
      (node (ref "C13") (pin "1") (pinfunction "1_1") (pintype "passive"))
      (node (ref "C14") (pin "2") (pinfunction "2_2") (pintype "passive"))
      (node (ref "C15") (pin "1") (pinfunction "1_1") (pintype "passive"))
      (node (ref "C16") (pin "2") (pinfunction "2_2") (pintype "passive"))
      (node (ref "C17") (pin "1") (pinfunction "1_1") (pintype "passive"))
      (node (ref "C18") (pin "1") (pinfunction "1_1") (pintype "passive"))
      (node (ref "C19") (pin "1") (pinfunction "1_1") (pintype "passive"))
      (node (ref "C2") (pin "1") (pinfunction "1_1") (pintype "passive"))
      (node (ref "C20") (pin "1") (pinfunction "1_1") (pintype "passive"))
      (node (ref "C21") (pin "1") (pinfunction "1_1") (pintype "passive"))
      (node (ref "C22") (pin "1") (pinfunction "1_1") (pintype "passive"))
      (node (ref "C23") (pin "1") (pinfunction "1_1") (pintype "passive"))
      (node (ref "C24") (pin "1") (pinfunction "1_1") (pintype "passive"))
      (node (ref "C25") (pin "1") (pinfunction "1_1") (pintype "passive"))
      (node (ref "C26") (pin "1") (pinfunction "1_1") (pintype "passive"))
      (node (ref "C27") (pin "1") (pinfunction "1_1") (pintype "passive"))
      (node (ref "C28") (pin "1") (pinfunction "1_1") (pintype "passive"))
      (node (ref "C29") (pin "1") (pinfunction "1_1") (pintype "passive"))
      (node (ref "C3") (pin "1") (pinfunction "1_1") (pintype "passive"))
      (node (ref "C30") (pin "1") (pinfunction "1_1") (pintype "passive"))
      (node (ref "C31") (pin "1") (pinfunction "1_1") (pintype "passive"))
      (node (ref "C32") (pin "1") (pinfunction "1_1") (pintype "passive"))
      (node (ref "C4") (pin "2") (pinfunction "2_2") (pintype "passive"))
      (node (ref "C5") (pin "2") (pinfunction "2_2") (pintype "passive"))
      (node (ref "C6") (pin "2") (pinfunction "2_2") (pintype "passive"))
      (node (ref "C7") (pin "2") (pinfunction "2_2") (pintype "passive"))
      (node (ref "C8") (pin "2") (pinfunction "2_2") (pintype "passive"))
      (node (ref "C9") (pin "1") (pinfunction "1_1") (pintype "passive"))
      (node (ref "ENY1") (pin "2") (pinfunction "K_2") (pintype "passive"))
      (node (ref "IC1") (pin "1") (pinfunction "GND_1") (pintype "passive"))
      (node (ref "JP1") (pin "1") (pinfunction "1_1") (pintype "passive"))
      (node (ref "P1") (pin "5") (pinfunction "5_5") (pintype "passive"))
      (node (ref "P1") (pin "6") (pinfunction "6_6") (pintype "passive"))
      (node (ref "P2") (pin "2") (pinfunction "2_2") (pintype "passive"))
      (node (ref "PiEnergy2") (pin "4") (pinfunction "GND_4") (pintype "passive"))
      (node (ref "PiEnergy2") (pin "7") (pinfunction "GND_7") (pintype "passive"))
      (node (ref "SW1") (pin "1") (pinfunction "1_1") (pintype "passive"))
      (node (ref "U1") (pin "1") (pinfunction "GND_1") (pintype "passive"))
      (node (ref "U2") (pin "107") (pinfunction "VSS_107") (pintype "passive"))
      (node (ref "U2") (pin "120") (pinfunction "VSS_120") (pintype "passive"))
      (node (ref "U2") (pin "130") (pinfunction "VSS_130") (pintype "passive"))
      (node (ref "U2") (pin "16") (pinfunction "VSS_16") (pintype "passive"))
      (node (ref "U2") (pin "31") (pinfunction "VSSA_31") (pintype "passive"))
      (node (ref "U2") (pin "38") (pinfunction "VSS_38") (pintype "passive"))
      (node (ref "U2") (pin "51") (pinfunction "VSS_51") (pintype "passive"))
      (node (ref "U2") (pin "61") (pinfunction "VSS_61") (pintype "passive"))
      (node (ref "U2") (pin "83") (pinfunction "VSS_83") (pintype "passive"))
      (node (ref "U2") (pin "94") (pinfunction "VSS_94") (pintype "passive"))
    )
    (net (code "121") (name "Net-(ENY1-A)") (class "Default")
      (node (ref "ENY1") (pin "1") (pinfunction "A_1") (pintype "passive"))
      (node (ref "R7") (pin "1") (pinfunction "1_1") (pintype "passive"))
    )
    (net (code "122") (name "Net-(IC1-DTR#)") (class "Default")
      (node (ref "IC1") (pin "13") (pinfunction "DTR#_13") (pintype "passive"))
      (node (ref "R4") (pin "2") (pinfunction "2_2") (pintype "passive"))
    )
    (net (code "123") (name "Net-(IC1-RTS#)") (class "Default")
      (node (ref "IC1") (pin "14") (pinfunction "RTS#_14") (pintype "passive"))
      (node (ref "Q1") (pin "2") (pinfunction "E_2") (pintype "passive"))
      (node (ref "R5") (pin "2") (pinfunction "2_2") (pintype "passive"))
    )
    (net (code "124") (name "Net-(IC1-V3)") (class "Default")
      (node (ref "C4") (pin "1") (pinfunction "1_1") (pintype "passive"))
      (node (ref "IC1") (pin "4") (pinfunction "V3_4") (pintype "passive"))
    )
    (net (code "125") (name "Net-(IC1-XI)") (class "Default")
      (node (ref "C5") (pin "1") (pinfunction "1_1") (pintype "passive"))
      (node (ref "IC1") (pin "7") (pinfunction "XI_7") (pintype "passive"))
      (node (ref "Y1") (pin "2") (pinfunction "OSC2_2") (pintype "passive"))
    )
    (net (code "126") (name "Net-(IC1-XO)") (class "Default")
      (node (ref "C6") (pin "1") (pinfunction "1_1") (pintype "passive"))
      (node (ref "IC1") (pin "8") (pinfunction "XO_8") (pintype "passive"))
      (node (ref "Y1") (pin "1") (pinfunction "OSC1_1") (pintype "passive"))
    )
    (net (code "127") (name "Net-(P1-Pad3)") (class "Default")
      (node (ref "P1") (pin "3") (pinfunction "3_3") (pintype "passive"))
      (node (ref "R1") (pin "2") (pinfunction "2_2") (pintype "passive"))
    )
    (net (code "128") (name "Net-(P1-Pad4)") (class "Default")
      (node (ref "P1") (pin "4") (pinfunction "4_4") (pintype "passive"))
      (node (ref "R2") (pin "1") (pinfunction "1_1") (pintype "passive"))
    )
    (net (code "129") (name "Net-(Q1-B)") (class "Default")
      (node (ref "Q1") (pin "1") (pinfunction "B_1") (pintype "passive"))
      (node (ref "R4") (pin "1") (pinfunction "1_1") (pintype "passive"))
    )
    (net (code "130") (name "Net-(Q1-C)") (class "Default")
      (node (ref "Q1") (pin "3") (pinfunction "C_3") (pintype "passive"))
      (node (ref "R3") (pin "1") (pinfunction "1_1") (pintype "passive"))
      (node (ref "VD1") (pin "2") (pinfunction "K_2") (pintype "passive"))
    )
    (net (code "131") (name "Net-(Q2-B)") (class "Default")
      (node (ref "Q2") (pin "1") (pinfunction "B_1") (pintype "passive"))
      (node (ref "R5") (pin "1") (pinfunction "1_1") (pintype "passive"))
    )
    (net (code "132") (name "Net-(Q2-C)") (class "Default")
      (node (ref "Q2") (pin "3") (pinfunction "C_3") (pintype "passive"))
      (node (ref "R6") (pin "2") (pinfunction "2_2") (pintype "passive"))
    )
    (net (code "133") (name "Net-(U2-OSC_IN{slash}PH0)") (class "Default")
      (node (ref "C12") (pin "1") (pinfunction "1_1") (pintype "passive"))
      (node (ref "R8") (pin "2") (pinfunction "2_2") (pintype "passive"))
      (node (ref "U2") (pin "23") (pinfunction "OSC_IN/PH0_23") (pintype "passive"))
      (node (ref "Y3") (pin "2") (pinfunction "OSC2_2") (pintype "passive"))
    )
    (net (code "134") (name "Net-(U2-OSC_OUT{slash}PH1)") (class "Default")
      (node (ref "C14") (pin "1") (pinfunction "1_1") (pintype "passive"))
      (node (ref "R8") (pin "1") (pinfunction "1_1") (pintype "passive"))
      (node (ref "U2") (pin "24") (pinfunction "OSC_OUT/PH1_24") (pintype "passive"))
      (node (ref "Y3") (pin "1") (pinfunction "OSC1_1") (pintype "passive"))
    )
    (net (code "135") (name "Net-(U2-PC14{slash}OSC32_IN)") (class "Default")
      (node (ref "C11") (pin "2") (pinfunction "2_2") (pintype "passive"))
      (node (ref "U2") (pin "8") (pinfunction "PC14/OSC32_IN_8") (pintype "passive"))
      (node (ref "Y2") (pin "1") (pinfunction "OSC1_1") (pintype "passive"))
    )
    (net (code "136") (name "Net-(U2-PC15{slash}OSC32_OUT)") (class "Default")
      (node (ref "C13") (pin "2") (pinfunction "2_2") (pintype "passive"))
      (node (ref "U2") (pin "9") (pinfunction "PC15/OSC32_OUT_9") (pintype "passive"))
      (node (ref "Y2") (pin "2") (pinfunction "OSC2_2") (pintype "passive"))
    )
    (net (code "137") (name "Net-(U2-PDR_ON)") (class "Default")
      (node (ref "R9") (pin "1") (pinfunction "1_1") (pintype "passive"))
      (node (ref "U2") (pin "143") (pinfunction "PDR_ON_143") (pintype "passive"))
    )
    (net (code "138") (name "Net-(U2-VCAP_1)") (class "Default")
      (node (ref "C18") (pin "2") (pinfunction "2_2") (pintype "passive"))
      (node (ref "U2") (pin "71") (pinfunction "VCAP_1_71") (pintype "passive"))
    )
    (net (code "139") (name "Net-(U2-VCAP_2)") (class "Default")
      (node (ref "C17") (pin "2") (pinfunction "2_2") (pintype "passive"))
      (node (ref "U2") (pin "106") (pinfunction "VCAP_2_106") (pintype "passive"))
    )
    (net (code "140") (name "unconnected-(IC1-CTS#-Pad9)") (class "Default")
      (node (ref "IC1") (pin "9") (pinfunction "CTS#_9") (pintype "passive"))
    )
    (net (code "141") (name "unconnected-(IC1-DCD#-Pad12)") (class "Default")
      (node (ref "IC1") (pin "12") (pinfunction "DCD#_12") (pintype "passive"))
    )
    (net (code "142") (name "unconnected-(IC1-DSR#-Pad10)") (class "Default")
      (node (ref "IC1") (pin "10") (pinfunction "DSR#_10") (pintype "passive"))
    )
    (net (code "143") (name "unconnected-(IC1-RI#-Pad11)") (class "Default")
      (node (ref "IC1") (pin "11") (pinfunction "RI#_11") (pintype "passive"))
    )
    (net (code "144") (name "unconnected-(IC1-RS232-Pad15)") (class "Default")
      (node (ref "IC1") (pin "15") (pinfunction "RS232_15") (pintype "passive"))
    )
    (net (code "145") (name "unconnected-(PiEnergy2-SHIDLE-Pad5)") (class "Default")
      (node (ref "PiEnergy2") (pin "5") (pinfunction "SHIDLE_5") (pintype "passive+no_connect"))
    )
    (net (code "146") (name "unconnected-(PiEnergy2-SHIELD-Pad6)") (class "Default")
      (node (ref "PiEnergy2") (pin "6") (pinfunction "SHIELD_6") (pintype "passive+no_connect"))
    )
    (net (code "147") (name "unconnected-(PiEnergy2-SHIELD-Pad8)") (class "Default")
      (node (ref "PiEnergy2") (pin "8") (pinfunction "SHIELD_8") (pintype "passive+no_connect"))
    )
    (net (code "148") (name "unconnected-(PiEnergy2-SHIELD-Pad9)") (class "Default")
      (node (ref "PiEnergy2") (pin "9") (pinfunction "SHIELD_9") (pintype "passive+no_connect"))
    )
  )
)
